# PicKit2Clone.net
KiCad netlist of a schematic drawn in EAGLE
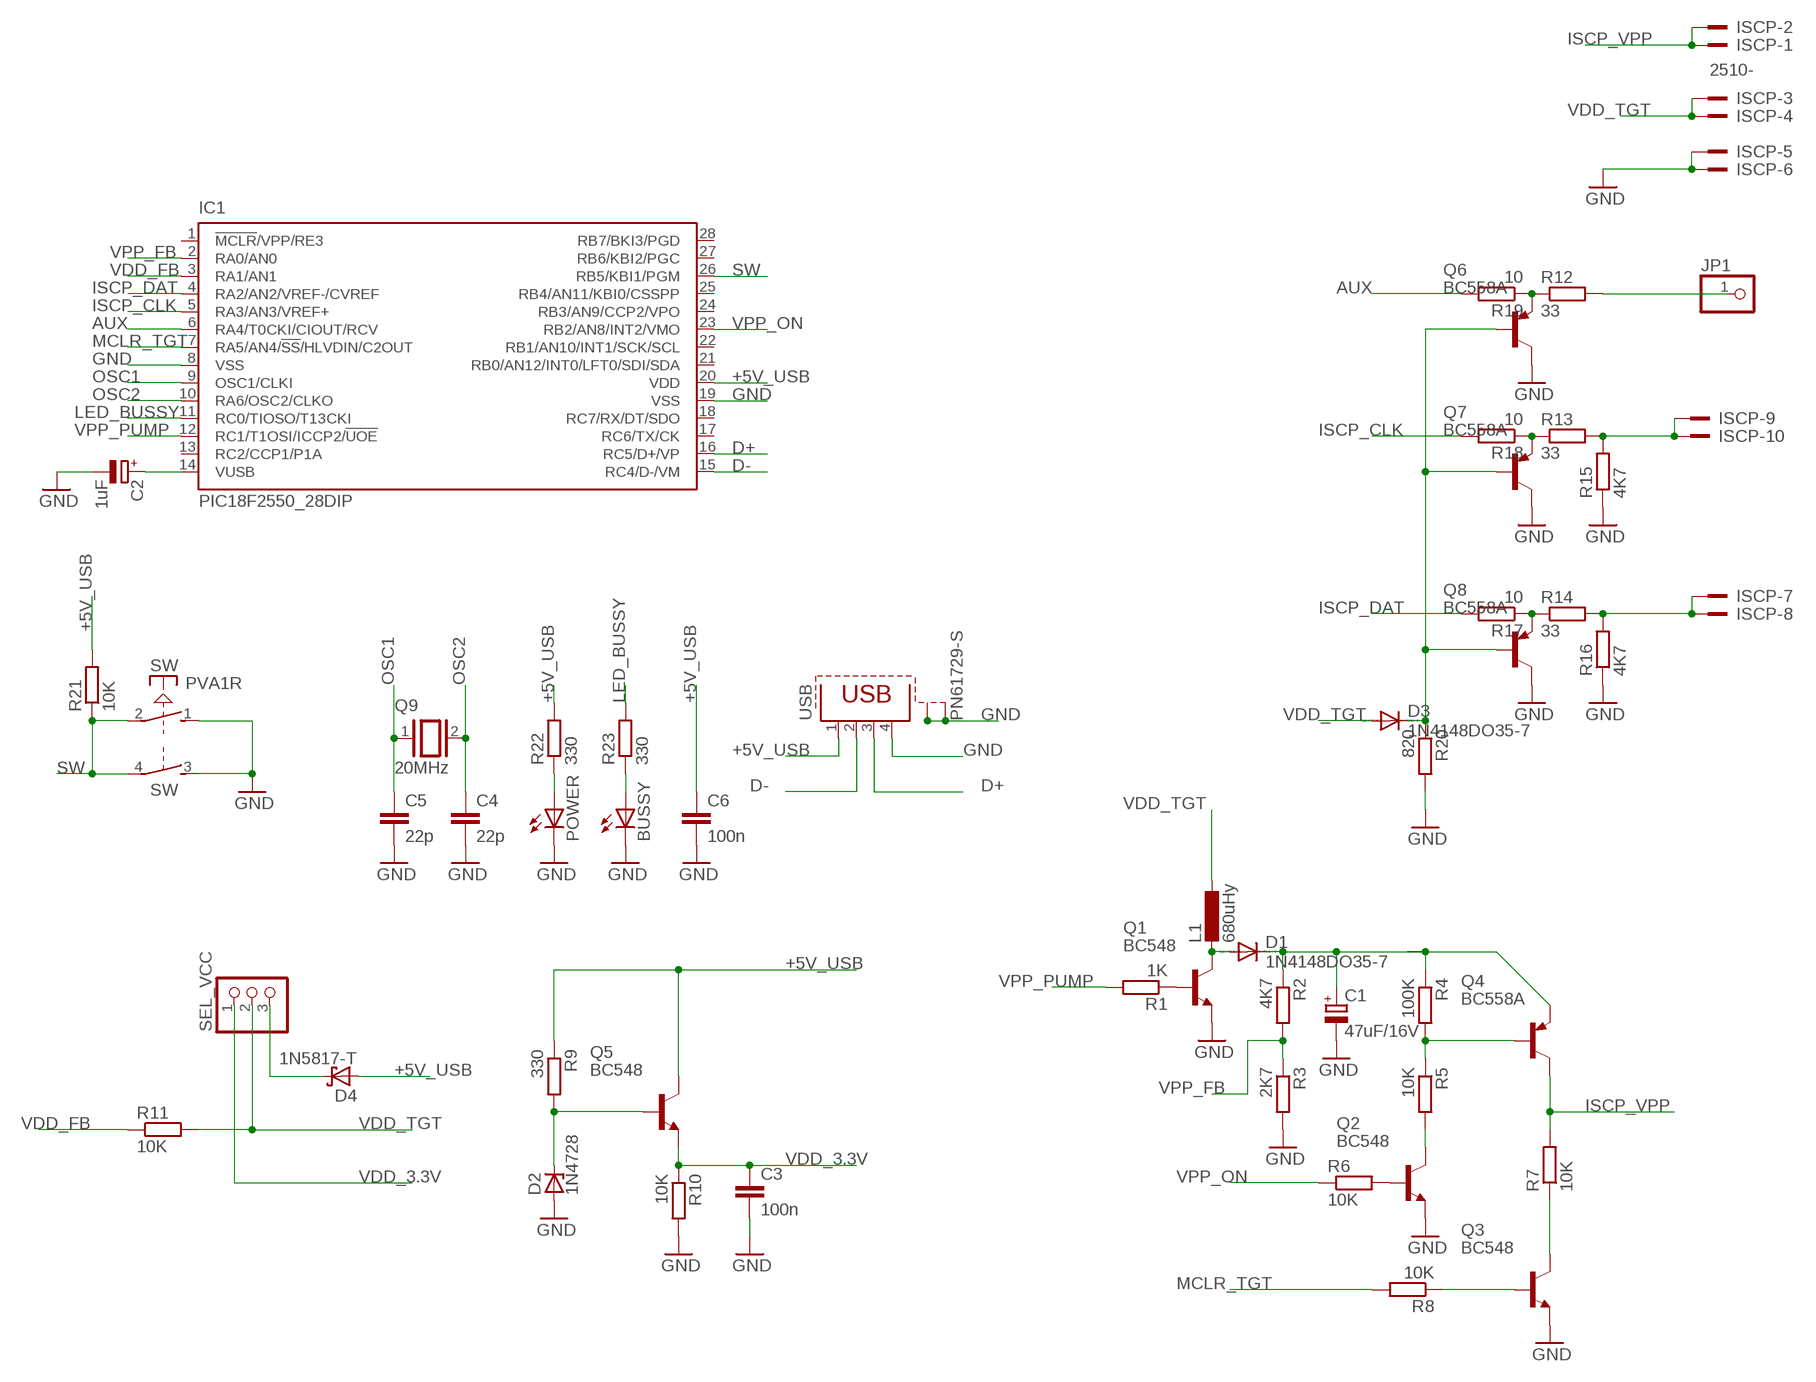
[diagram p0: schematic, sheet 1]

(export (version "E")
  (design (tool "Eeschema 10.0.6"))
  (components
    (comp (ref "BUSSY")
      (value "LED5MM")
      (footprint "eagle-import:LED5MM")
      (libsource (lib "eagle-import") (part "LED5MM"))
    )
    (comp (ref "C1")
      (value "47uF/16V")
      (footprint "eagle-import:E1,8-4")
      (libsource (lib "eagle-import") (part "CPOL-EUE1.8-4"))
    )
    (comp (ref "C2")
      (value "1uF")
      (footprint "eagle-import:E1,8-4")
      (libsource (lib "eagle-import") (part "CPOL-EUE1.8-4"))
    )
    (comp (ref "C3")
      (value "100n")
      (footprint "eagle-import:C025-025X050")
      (libsource (lib "eagle-import") (part "C-EU025-025X050"))
    )
    (comp (ref "C4")
      (value "22p")
      (footprint "eagle-import:C025-024X044")
      (libsource (lib "eagle-import") (part "C-EU025-024X044"))
    )
    (comp (ref "C5")
      (value "22p")
      (footprint "eagle-import:C025-024X044")
      (libsource (lib "eagle-import") (part "C-EU025-024X044"))
    )
    (comp (ref "C6")
      (value "100n")
      (footprint "eagle-import:C025-024X044")
      (libsource (lib "eagle-import") (part "C-EU025-024X044"))
    )
    (comp (ref "D1")
      (value "1N4148DO35-7")
      (footprint "eagle-import:DO35-7")
      (libsource (lib "eagle-import") (part "1N4148DO35-7"))
    )
    (comp (ref "D2")
      (value "1N4728")
      (footprint "eagle-import:DO41Z10")
      (libsource (lib "eagle-import") (part "1N4728"))
    )
    (comp (ref "D3")
      (value "1N4148DO35-7")
      (footprint "eagle-import:DO35-7")
      (libsource (lib "eagle-import") (part "1N4148DO35-7"))
    )
    (comp (ref "D4")
      (value "1N5817-T")
      (footprint "eagle-import:DO41-7.6")
      (libsource (lib "eagle-import") (part "1N5817-T"))
    )
    (comp (ref "IC1")
      (value "PIC18F2550_28DIP")
      (footprint "eagle-import:DIL28-3")
      (fields (field (name "MF") "MICROCHIP") (field (name "MPN") "PIC18F2550-I/SP"))
      (libsource (lib "eagle-import") (part "PIC18F2_28DIP550"))
    )
    (comp (ref "ISCP")
      (value "2510-")
      (footprint "eagle-import:PAK100_2500-10")
      (fields (field (name "MF") "3M") (field (name "MPN") "2510-6002UB"))
      (libsource (lib "eagle-import") (part "2510-"))
    )
    (comp (ref "JP1")
      (value "PINHD-1X1")
      (footprint "eagle-import:1X01")
      (libsource (lib "eagle-import") (part "PINHD-1X1"))
    )
    (comp (ref "L1")
      (value "680uHy")
      (footprint "eagle-import:0204_5")
      (libsource (lib "eagle-import") (part "L-EU0204/5"))
    )
    (comp (ref "POWER")
      (value "LED5MM")
      (footprint "eagle-import:LED5MM")
      (libsource (lib "eagle-import") (part "LED5MM"))
    )
    (comp (ref "Q1")
      (value "BC548")
      (footprint "eagle-import:TO92-EBC")
      (libsource (lib "eagle-import") (part "BC548"))
    )
    (comp (ref "Q2")
      (value "BC548")
      (footprint "eagle-import:TO92-EBC")
      (libsource (lib "eagle-import") (part "BC548"))
    )
    (comp (ref "Q3")
      (value "BC548")
      (footprint "eagle-import:TO92-EBC")
      (libsource (lib "eagle-import") (part "BC548"))
    )
    (comp (ref "Q4")
      (value "BC558A")
      (footprint "eagle-import:TO92-EBC")
      (libsource (lib "eagle-import") (part "BC558A"))
    )
    (comp (ref "Q5")
      (value "BC548")
      (footprint "eagle-import:TO92-EBC")
      (libsource (lib "eagle-import") (part "BC548"))
    )
    (comp (ref "Q6")
      (value "BC558A")
      (footprint "eagle-import:TO92-EBC")
      (libsource (lib "eagle-import") (part "BC558A"))
    )
    (comp (ref "Q7")
      (value "BC558A")
      (footprint "eagle-import:TO92-EBC")
      (libsource (lib "eagle-import") (part "BC558A"))
    )
    (comp (ref "Q8")
      (value "BC558A")
      (footprint "eagle-import:TO92-EBC")
      (libsource (lib "eagle-import") (part "BC558A"))
    )
    (comp (ref "Q9")
      (value "20MHz")
      (footprint "eagle-import:QS")
      (libsource (lib "eagle-import") (part "XTAL/S"))
    )
    (comp (ref "R1")
      (value "1K")
      (footprint "eagle-import:0207_10")
      (libsource (lib "eagle-import") (part "R-EU_0207/10"))
    )
    (comp (ref "R2")
      (value "4K7")
      (footprint "eagle-import:0204_5")
      (libsource (lib "eagle-import") (part "R-EU_0204/5"))
    )
    (comp (ref "R3")
      (value "2K7")
      (footprint "eagle-import:0204_5")
      (libsource (lib "eagle-import") (part "R-EU_0204/5"))
    )
    (comp (ref "R4")
      (value "100K")
      (footprint "eagle-import:0204_5")
      (libsource (lib "eagle-import") (part "R-EU_0204/5"))
    )
    (comp (ref "R5")
      (value "10K")
      (footprint "eagle-import:0204_5")
      (libsource (lib "eagle-import") (part "R-EU_0204/5"))
    )
    (comp (ref "R6")
      (value "10K")
      (footprint "eagle-import:0204_7")
      (libsource (lib "eagle-import") (part "R-EU_0204/7"))
    )
    (comp (ref "R7")
      (value "10K")
      (footprint "eagle-import:0204_5")
      (libsource (lib "eagle-import") (part "R-EU_0204/5"))
    )
    (comp (ref "R8")
      (value "10K")
      (footprint "eagle-import:0204_5")
      (libsource (lib "eagle-import") (part "R-EU_0204/5"))
    )
    (comp (ref "R9")
      (value "330")
      (footprint "eagle-import:0204_5")
      (libsource (lib "eagle-import") (part "R-EU_0204/5"))
    )
    (comp (ref "R10")
      (value "10K")
      (footprint "eagle-import:0204_5")
      (libsource (lib "eagle-import") (part "R-EU_0204/5"))
    )
    (comp (ref "R11")
      (value "10K")
      (footprint "eagle-import:0204_5")
      (libsource (lib "eagle-import") (part "R-EU_0204/5"))
    )
    (comp (ref "R12")
      (value "33")
      (footprint "eagle-import:0204_5")
      (libsource (lib "eagle-import") (part "R-EU_0204/5"))
    )
    (comp (ref "R13")
      (value "33")
      (footprint "eagle-import:0204_5")
      (libsource (lib "eagle-import") (part "R-EU_0204/5"))
    )
    (comp (ref "R14")
      (value "33")
      (footprint "eagle-import:0204_5")
      (libsource (lib "eagle-import") (part "R-EU_0204/5"))
    )
    (comp (ref "R15")
      (value "4K7")
      (footprint "eagle-import:0204_5")
      (libsource (lib "eagle-import") (part "R-EU_0204/5"))
    )
    (comp (ref "R16")
      (value "4K7")
      (footprint "eagle-import:0204_5")
      (libsource (lib "eagle-import") (part "R-EU_0204/5"))
    )
    (comp (ref "R17")
      (value "10")
      (footprint "eagle-import:0204_5")
      (libsource (lib "eagle-import") (part "R-EU_0204/5"))
    )
    (comp (ref "R18")
      (value "10")
      (footprint "eagle-import:0204_5")
      (libsource (lib "eagle-import") (part "R-EU_0204/5"))
    )
    (comp (ref "R19")
      (value "10")
      (footprint "eagle-import:0204_5")
      (libsource (lib "eagle-import") (part "R-EU_0204/5"))
    )
    (comp (ref "R20")
      (value "820")
      (footprint "eagle-import:0204_5")
      (libsource (lib "eagle-import") (part "R-EU_0204/5"))
    )
    (comp (ref "R21")
      (value "10K")
      (footprint "eagle-import:0204_5")
      (libsource (lib "eagle-import") (part "R-EU_0204/5"))
    )
    (comp (ref "R22")
      (value "330")
      (footprint "eagle-import:0204_5")
      (libsource (lib "eagle-import") (part "R-EU_0204/5"))
    )
    (comp (ref "R23")
      (value "330")
      (footprint "eagle-import:0204_5")
      (libsource (lib "eagle-import") (part "R-EU_0204/5"))
    )
    (comp (ref "SEL_VCC")
      (value "PINHD-1X3")
      (footprint "eagle-import:1X03")
      (libsource (lib "eagle-import") (part "PINHD-1X3"))
    )
    (comp (ref "SW")
      (value "PVA1R")
      (footprint "eagle-import:PVA1R")
      (libsource (lib "eagle-import") (part "PVA1R"))
    )
    (comp (ref "USB")
      (value "PN61729-S")
      (footprint "eagle-import:PN61729-S")
      (libsource (lib "eagle-import") (part "PN61729-S"))
    )
  )
  (nets
    (net (code "1") (name "/+5V_USB") (class "Default")
      (node (ref "C6") (pin "1") (pinfunction "1_1") (pintype "passive"))
      (node (ref "D4") (pin "A") (pinfunction "A_A") (pintype "passive"))
      (node (ref "IC1") (pin "20") (pinfunction "VDD_20") (pintype "power_in"))
      (node (ref "Q5") (pin "C") (pinfunction "C_C") (pintype "passive"))
      (node (ref "R21") (pin "2") (pinfunction "2_2") (pintype "passive"))
      (node (ref "R22") (pin "2") (pinfunction "2_2") (pintype "passive"))
      (node (ref "R9") (pin "1") (pinfunction "1_1") (pintype "passive"))
      (node (ref "USB") (pin "1") (pinfunction "1_1") (pintype "passive"))
    )
    (net (code "2") (name "/AUX") (class "Default")
      (node (ref "IC1") (pin "6") (pinfunction "RA4/T0CKI/CIOUT/RCV_6") (pintype "bidirectional"))
      (node (ref "R19") (pin "2") (pinfunction "2_2") (pintype "passive"))
    )
    (net (code "3") (name "/D+") (class "Default")
      (node (ref "IC1") (pin "16") (pinfunction "RC5/D+/VP_16") (pintype "bidirectional"))
      (node (ref "USB") (pin "3") (pinfunction "3_3") (pintype "passive"))
    )
    (net (code "4") (name "/D-") (class "Default")
      (node (ref "IC1") (pin "15") (pinfunction "RC4/D-/VM_15") (pintype "bidirectional"))
      (node (ref "USB") (pin "2") (pinfunction "2_2") (pintype "passive"))
    )
    (net (code "5") (name "/ISCP_CLK") (class "Default")
      (node (ref "IC1") (pin "5") (pinfunction "RA3/AN3/VREF+_5") (pintype "bidirectional"))
      (node (ref "R18") (pin "2") (pinfunction "2_2") (pintype "passive"))
    )
    (net (code "6") (name "/ISCP_DAT") (class "Default")
      (node (ref "IC1") (pin "4") (pinfunction "RA2/AN2/VREF-/CVREF_4") (pintype "bidirectional"))
      (node (ref "R17") (pin "2") (pinfunction "2_2") (pintype "passive"))
    )
    (net (code "7") (name "/ISCP_VPP") (class "Default")
      (node (ref "ISCP") (pin "1") (pinfunction "KL_1") (pintype "passive"))
      (node (ref "ISCP") (pin "2") (pinfunction "KL_2") (pintype "passive"))
      (node (ref "Q4") (pin "C") (pinfunction "C_C") (pintype "passive"))
      (node (ref "R7") (pin "2") (pinfunction "2_2") (pintype "passive"))
    )
    (net (code "8") (name "/LED_BUSSY") (class "Default")
      (node (ref "IC1") (pin "11") (pinfunction "RC0/TIOSO/T13CKI_11") (pintype "bidirectional"))
      (node (ref "R23") (pin "2") (pinfunction "2_2") (pintype "passive"))
    )
    (net (code "9") (name "/MCLR_TGT") (class "Default")
      (node (ref "IC1") (pin "7") (pinfunction "RA5/AN4/~{SS}/HLVDIN/C2OUT_7") (pintype "bidirectional"))
      (node (ref "R8") (pin "2") (pinfunction "2_2") (pintype "passive"))
    )
    (net (code "10") (name "/OSC1") (class "Default")
      (node (ref "C5") (pin "1") (pinfunction "1_1") (pintype "passive"))
      (node (ref "IC1") (pin "9") (pinfunction "OSC1/CLKI_9") (pintype "input"))
      (node (ref "Q9") (pin "1") (pinfunction "1_1") (pintype "passive"))
    )
    (net (code "11") (name "/OSC2") (class "Default")
      (node (ref "C4") (pin "1") (pinfunction "1_1") (pintype "passive"))
      (node (ref "IC1") (pin "10") (pinfunction "RA6/OSC2/CLKO_10") (pintype "output"))
      (node (ref "Q9") (pin "2") (pinfunction "2_2") (pintype "passive"))
    )
    (net (code "12") (name "/SW") (class "Default")
      (node (ref "IC1") (pin "26") (pinfunction "RB5/KBI1/PGM_26") (pintype "bidirectional"))
      (node (ref "R21") (pin "1") (pinfunction "1_1") (pintype "passive"))
      (node (ref "SW") (pin "2") (pinfunction "P_2") (pintype "passive"))
      (node (ref "SW") (pin "4") (pinfunction "P_4") (pintype "passive"))
    )
    (net (code "13") (name "/VDD_3.3V") (class "Default")
      (node (ref "C3") (pin "1") (pinfunction "1_1") (pintype "passive"))
      (node (ref "Q5") (pin "E") (pinfunction "E_E") (pintype "passive"))
      (node (ref "R10") (pin "1") (pinfunction "1_1") (pintype "passive"))
      (node (ref "SEL_VCC") (pin "1") (pinfunction "1_1") (pintype "passive"))
    )
    (net (code "14") (name "/VDD_FB") (class "Default")
      (node (ref "IC1") (pin "3") (pinfunction "RA1/AN1_3") (pintype "bidirectional"))
      (node (ref "R11") (pin "1") (pinfunction "1_1") (pintype "passive"))
    )
    (net (code "15") (name "/VDD_TGT") (class "Default")
      (node (ref "D3") (pin "A") (pinfunction "A_A") (pintype "passive"))
      (node (ref "ISCP") (pin "3") (pinfunction "KL_3") (pintype "passive"))
      (node (ref "ISCP") (pin "4") (pinfunction "KL_4") (pintype "passive"))
      (node (ref "L1") (pin "1") (pinfunction "1_1") (pintype "passive"))
      (node (ref "R11") (pin "2") (pinfunction "2_2") (pintype "passive"))
      (node (ref "SEL_VCC") (pin "2") (pinfunction "2_2") (pintype "passive"))
    )
    (net (code "16") (name "/VPP_FB") (class "Default")
      (node (ref "IC1") (pin "2") (pinfunction "RA0/AN0_2") (pintype "bidirectional"))
      (node (ref "R2") (pin "2") (pinfunction "2_2") (pintype "passive"))
      (node (ref "R3") (pin "1") (pinfunction "1_1") (pintype "passive"))
    )
    (net (code "17") (name "/VPP_ON") (class "Default")
      (node (ref "IC1") (pin "23") (pinfunction "RB2/AN8/INT2/VMO_23") (pintype "bidirectional"))
      (node (ref "R6") (pin "1") (pinfunction "1_1") (pintype "passive"))
    )
    (net (code "18") (name "/VPP_PUMP") (class "Default")
      (node (ref "IC1") (pin "12") (pinfunction "RC1/T1OSI/ICCP2/~{UOE}_12") (pintype "bidirectional"))
      (node (ref "R1") (pin "2") (pinfunction "2_2") (pintype "passive"))
    )
    (net (code "19") (name "GND") (class "Default")
      (node (ref "BUSSY") (pin "K") (pinfunction "C_K") (pintype "passive"))
      (node (ref "C1") (pin "-") (pinfunction "-_-") (pintype "passive"))
      (node (ref "C2") (pin "-") (pinfunction "-_-") (pintype "passive"))
      (node (ref "C3") (pin "2") (pinfunction "2_2") (pintype "passive"))
      (node (ref "C4") (pin "2") (pinfunction "2_2") (pintype "passive"))
      (node (ref "C5") (pin "2") (pinfunction "2_2") (pintype "passive"))
      (node (ref "C6") (pin "2") (pinfunction "2_2") (pintype "passive"))
      (node (ref "D2") (pin "A") (pinfunction "A_A") (pintype "passive"))
      (node (ref "IC1") (pin "19") (pinfunction "VSS_19") (pintype "power_in"))
      (node (ref "IC1") (pin "8") (pinfunction "VSS_8") (pintype "power_in"))
      (node (ref "ISCP") (pin "5") (pinfunction "KL_5") (pintype "passive"))
      (node (ref "ISCP") (pin "6") (pinfunction "KL_6") (pintype "passive"))
      (node (ref "POWER") (pin "K") (pinfunction "C_K") (pintype "passive"))
      (node (ref "Q1") (pin "E") (pinfunction "E_E") (pintype "passive"))
      (node (ref "Q2") (pin "E") (pinfunction "E_E") (pintype "passive"))
      (node (ref "Q3") (pin "E") (pinfunction "E_E") (pintype "passive"))
      (node (ref "Q6") (pin "C") (pinfunction "C_C") (pintype "passive"))
      (node (ref "Q7") (pin "C") (pinfunction "C_C") (pintype "passive"))
      (node (ref "Q8") (pin "C") (pinfunction "C_C") (pintype "passive"))
      (node (ref "R10") (pin "2") (pinfunction "2_2") (pintype "passive"))
      (node (ref "R15") (pin "1") (pinfunction "1_1") (pintype "passive"))
      (node (ref "R16") (pin "1") (pinfunction "1_1") (pintype "passive"))
      (node (ref "R20") (pin "2") (pinfunction "2_2") (pintype "passive"))
      (node (ref "R3") (pin "2") (pinfunction "2_2") (pintype "passive"))
      (node (ref "SW") (pin "1") (pinfunction "S_1") (pintype "passive"))
      (node (ref "SW") (pin "3") (pinfunction "S_3") (pintype "passive"))
      (node (ref "USB") (pin "4") (pinfunction "4_4") (pintype "passive"))
      (node (ref "USB") (pin "S1") (pinfunction "S1_S1") (pintype "passive"))
      (node (ref "USB") (pin "S2") (pinfunction "S2_S2") (pintype "passive"))
    )
    (net (code "20") (name "Net-(BUSSY-PadA)") (class "Default")
      (node (ref "BUSSY") (pin "A") (pinfunction "A_A") (pintype "passive"))
      (node (ref "R23") (pin "1") (pinfunction "1_1") (pintype "passive"))
    )
    (net (code "21") (name "Net-(C1-Pad+)") (class "Default")
      (node (ref "C1") (pin "+") (pinfunction "+_+") (pintype "passive"))
      (node (ref "D1") (pin "C") (pinfunction "C_C") (pintype "passive"))
      (node (ref "Q4") (pin "E") (pinfunction "E_E") (pintype "passive"))
      (node (ref "R2") (pin "1") (pinfunction "1_1") (pintype "passive"))
      (node (ref "R4") (pin "1") (pinfunction "1_1") (pintype "passive"))
    )
    (net (code "22") (name "Net-(D1-PadA)") (class "Default")
      (node (ref "D1") (pin "A") (pinfunction "A_A") (pintype "passive"))
      (node (ref "L1") (pin "2") (pinfunction "2_2") (pintype "passive"))
      (node (ref "Q1") (pin "C") (pinfunction "C_C") (pintype "passive"))
    )
    (net (code "23") (name "Net-(D2-PadC)") (class "Default")
      (node (ref "D2") (pin "C") (pinfunction "C_C") (pintype "passive"))
      (node (ref "Q5") (pin "B") (pinfunction "B_B") (pintype "passive"))
      (node (ref "R9") (pin "2") (pinfunction "2_2") (pintype "passive"))
    )
    (net (code "24") (name "Net-(D3-PadC)") (class "Default")
      (node (ref "D3") (pin "C") (pinfunction "C_C") (pintype "passive"))
      (node (ref "Q6") (pin "B") (pinfunction "B_B") (pintype "passive"))
      (node (ref "Q7") (pin "B") (pinfunction "B_B") (pintype "passive"))
      (node (ref "Q8") (pin "B") (pinfunction "B_B") (pintype "passive"))
      (node (ref "R20") (pin "1") (pinfunction "1_1") (pintype "passive"))
    )
    (net (code "25") (name "Net-(D4-PadC)") (class "Default")
      (node (ref "D4") (pin "C") (pinfunction "C_C") (pintype "passive"))
      (node (ref "SEL_VCC") (pin "3") (pinfunction "3_3") (pintype "passive"))
    )
    (net (code "26") (name "Net-(IC1-VUSB)") (class "Default")
      (node (ref "C2") (pin "+") (pinfunction "+_+") (pintype "passive"))
      (node (ref "IC1") (pin "14") (pinfunction "VUSB_14") (pintype "bidirectional"))
    )
    (net (code "27") (name "Net-(ISCPB-KL)") (class "Default")
      (node (ref "ISCP") (pin "10") (pinfunction "KL_10") (pintype "passive"))
      (node (ref "ISCP") (pin "9") (pinfunction "KL_9") (pintype "passive"))
      (node (ref "R13") (pin "2") (pinfunction "2_2") (pintype "passive"))
      (node (ref "R15") (pin "2") (pinfunction "2_2") (pintype "passive"))
    )
    (net (code "28") (name "Net-(ISCPH-KL)") (class "Default")
      (node (ref "ISCP") (pin "7") (pinfunction "KL_7") (pintype "passive"))
      (node (ref "ISCP") (pin "8") (pinfunction "KL_8") (pintype "passive"))
      (node (ref "R14") (pin "2") (pinfunction "2_2") (pintype "passive"))
      (node (ref "R16") (pin "2") (pinfunction "2_2") (pintype "passive"))
    )
    (net (code "29") (name "Net-(JP1-Pad1)") (class "Default")
      (node (ref "JP1") (pin "1") (pinfunction "1_1") (pintype "passive"))
      (node (ref "R12") (pin "2") (pinfunction "2_2") (pintype "passive"))
    )
    (net (code "30") (name "Net-(POWER-PadA)") (class "Default")
      (node (ref "POWER") (pin "A") (pinfunction "A_A") (pintype "passive"))
      (node (ref "R22") (pin "1") (pinfunction "1_1") (pintype "passive"))
    )
    (net (code "31") (name "Net-(Q1-PadB)") (class "Default")
      (node (ref "Q1") (pin "B") (pinfunction "B_B") (pintype "passive"))
      (node (ref "R1") (pin "1") (pinfunction "1_1") (pintype "passive"))
    )
    (net (code "32") (name "Net-(Q2-PadB)") (class "Default")
      (node (ref "Q2") (pin "B") (pinfunction "B_B") (pintype "passive"))
      (node (ref "R6") (pin "2") (pinfunction "2_2") (pintype "passive"))
    )
    (net (code "33") (name "Net-(Q2-PadC)") (class "Default")
      (node (ref "Q2") (pin "C") (pinfunction "C_C") (pintype "passive"))
      (node (ref "R5") (pin "2") (pinfunction "2_2") (pintype "passive"))
    )
    (net (code "34") (name "Net-(Q3-PadB)") (class "Default")
      (node (ref "Q3") (pin "B") (pinfunction "B_B") (pintype "passive"))
      (node (ref "R8") (pin "1") (pinfunction "1_1") (pintype "passive"))
    )
    (net (code "35") (name "Net-(Q3-PadC)") (class "Default")
      (node (ref "Q3") (pin "C") (pinfunction "C_C") (pintype "passive"))
      (node (ref "R7") (pin "1") (pinfunction "1_1") (pintype "passive"))
    )
    (net (code "36") (name "Net-(Q4-PadB)") (class "Default")
      (node (ref "Q4") (pin "B") (pinfunction "B_B") (pintype "passive"))
      (node (ref "R4") (pin "2") (pinfunction "2_2") (pintype "passive"))
      (node (ref "R5") (pin "1") (pinfunction "1_1") (pintype "passive"))
    )
    (net (code "37") (name "Net-(Q6-PadE)") (class "Default")
      (node (ref "Q6") (pin "E") (pinfunction "E_E") (pintype "passive"))
      (node (ref "R12") (pin "1") (pinfunction "1_1") (pintype "passive"))
      (node (ref "R19") (pin "1") (pinfunction "1_1") (pintype "passive"))
    )
    (net (code "38") (name "Net-(Q7-PadE)") (class "Default")
      (node (ref "Q7") (pin "E") (pinfunction "E_E") (pintype "passive"))
      (node (ref "R13") (pin "1") (pinfunction "1_1") (pintype "passive"))
      (node (ref "R18") (pin "1") (pinfunction "1_1") (pintype "passive"))
    )
    (net (code "39") (name "Net-(Q8-PadE)") (class "Default")
      (node (ref "Q8") (pin "E") (pinfunction "E_E") (pintype "passive"))
      (node (ref "R14") (pin "1") (pinfunction "1_1") (pintype "passive"))
      (node (ref "R17") (pin "1") (pinfunction "1_1") (pintype "passive"))
    )
    (net (code "40") (name "unconnected-(IC1-RB0{slash}AN12{slash}INT0{slash}LFT0{slash}SDI{slash}SDA-Pad21)") (class "Default")
      (node (ref "IC1") (pin "21") (pinfunction "RB0/AN12/INT0/LFT0/SDI/SDA_21") (pintype "bidirectional"))
    )
    (net (code "41") (name "unconnected-(IC1-RB1{slash}AN10{slash}INT1{slash}SCK{slash}SCL-Pad22)") (class "Default")
      (node (ref "IC1") (pin "22") (pinfunction "RB1/AN10/INT1/SCK/SCL_22") (pintype "bidirectional"))
    )
    (net (code "42") (name "unconnected-(IC1-RB3{slash}AN9{slash}CCP2{slash}VPO-Pad24)") (class "Default")
      (node (ref "IC1") (pin "24") (pinfunction "RB3/AN9/CCP2/VPO_24") (pintype "bidirectional"))
    )
    (net (code "43") (name "unconnected-(IC1-RB4{slash}AN11{slash}KBI0{slash}CSSPP-Pad25)") (class "Default")
      (node (ref "IC1") (pin "25") (pinfunction "RB4/AN11/KBI0/CSSPP_25") (pintype "bidirectional"))
    )
    (net (code "44") (name "unconnected-(IC1-RB6{slash}KBI2{slash}PGC-Pad27)") (class "Default")
      (node (ref "IC1") (pin "27") (pinfunction "RB6/KBI2/PGC_27") (pintype "bidirectional"))
    )
    (net (code "45") (name "unconnected-(IC1-RB7{slash}BKI3{slash}PGD-Pad28)") (class "Default")
      (node (ref "IC1") (pin "28") (pinfunction "RB7/BKI3/PGD_28") (pintype "bidirectional"))
    )
    (net (code "46") (name "unconnected-(IC1-RC2{slash}CCP1{slash}P1A-Pad13)") (class "Default")
      (node (ref "IC1") (pin "13") (pinfunction "RC2/CCP1/P1A_13") (pintype "bidirectional"))
    )
    (net (code "47") (name "unconnected-(IC1-RC6{slash}TX{slash}CK-Pad17)") (class "Default")
      (node (ref "IC1") (pin "17") (pinfunction "RC6/TX/CK_17") (pintype "bidirectional"))
    )
    (net (code "48") (name "unconnected-(IC1-RC7{slash}RX{slash}DT{slash}SDO-Pad18)") (class "Default")
      (node (ref "IC1") (pin "18") (pinfunction "RC7/RX/DT/SDO_18") (pintype "bidirectional"))
    )
    (net (code "49") (name "unconnected-(IC1-~{MCLR}{slash}VPP{slash}RE3-Pad1)") (class "Default")
      (node (ref "IC1") (pin "1") (pinfunction "~{MCLR}/VPP/RE3_1") (pintype "input"))
    )
  )
)
